# 01.net
KiCad netlist of a schematic drawn in Altium Designer
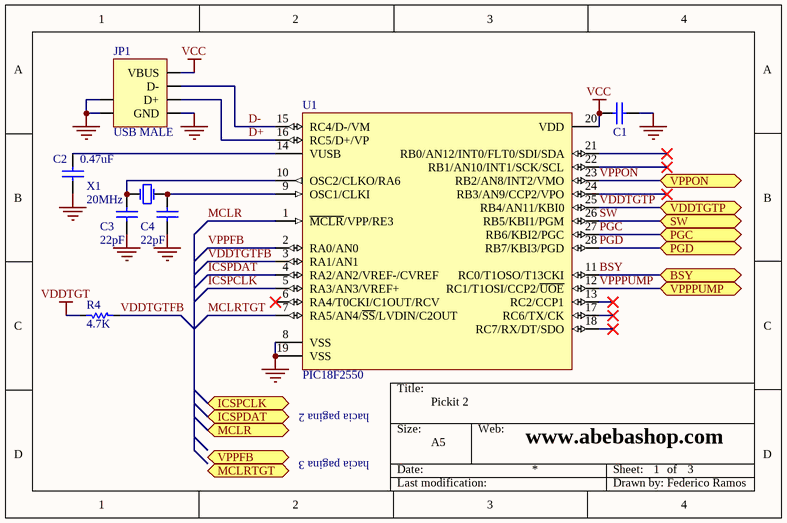
[diagram p0: 01.SchDoc]

(export (version "E")
  (design (tool "Eeschema 10.0.6"))
  (components
    (comp (ref "C1")
      (value "Cap")
      (footprint "1206NP")
      (description "Capacitor")
      (fields (field (name "VOLTAGE") "50V"))
      (libsource (lib "FEDE") (part "Cap"))
    )
    (comp (ref "C2")
      (value "0.47uF")
      (footprint "1206NP")
      (description "Capacitor")
      (fields (field (name "VOLTAGE") "50V") (field (name "Comment") "Cap"))
      (libsource (lib "FEDE") (part "Cap"))
    )
    (comp (ref "C3")
      (value "22pF")
      (footprint "1206NP")
      (description "Capacitor")
      (fields (field (name "VOLTAGE") "50V") (field (name "Comment") "Cap"))
      (libsource (lib "FEDE") (part "Cap"))
    )
    (comp (ref "C4")
      (value "22pF")
      (footprint "1206NP")
      (description "Capacitor")
      (fields (field (name "VOLTAGE") "50V") (field (name "Comment") "Cap"))
      (libsource (lib "FEDE") (part "Cap"))
    )
    (comp (ref "JP1")
      (value "USB MALE")
      (footprint "USB_A_MALE")
      (description "USB Connector")
      (libsource (lib "FEDE") (part "USB"))
    )
    (comp (ref "R4")
      (value "4.7K")
      (footprint "1206NP")
      (description "Resistor")
      (fields (field (name "POWER") "0.25W") (field (name "Comment") "Res"))
      (libsource (lib "FEDE") (part "Res"))
    )
    (comp (ref "U1")
      (value "PIC18F2550")
      (footprint "soic28")
      (description "Enhanced FLASH Microcontroller")
      (libsource (lib "FEDE") (part "PIC18F2550"))
    )
    (comp (ref "X1")
      (value "20MHz")
      (footprint "XTAL1")
      (description "Crystal Oscillator")
      (fields (field (name "Comment") "XTAL"))
      (libsource (lib "FEDE") (part "XTAL"))
    )
  )
  (nets
    (net (code "1") (name "/BSY") (class "Default")
      (node (ref "U1") (pin "11") (pinfunction "RC0/T1OSO/T13CKI_11") (pintype "bidirectional"))
    )
    (net (code "2") (name "/D+") (class "Default")
      (node (ref "JP1") (pin "3") (pinfunction "D+_3") (pintype "passive"))
      (node (ref "U1") (pin "16") (pinfunction "RC5/D+/VP_16") (pintype "bidirectional"))
    )
    (net (code "3") (name "/D-") (class "Default")
      (node (ref "JP1") (pin "2") (pinfunction "D-_2") (pintype "passive"))
      (node (ref "U1") (pin "15") (pinfunction "RC4/D-/VM_15") (pintype "bidirectional"))
    )
    (net (code "4") (name "/ICSPCLK") (class "Default")
      (node (ref "U1") (pin "5") (pinfunction "RA3/AN3/VREF+_5") (pintype "bidirectional"))
    )
    (net (code "5") (name "/ICSPDAT") (class "Default")
      (node (ref "U1") (pin "4") (pinfunction "RA2/AN2/VREF-/CVREF_4") (pintype "bidirectional"))
    )
    (net (code "6") (name "/MCLR") (class "Default")
      (node (ref "U1") (pin "1") (pinfunction "~{MCLR}/VPP/RE3_1") (pintype "input"))
    )
    (net (code "7") (name "/MCLRTGT") (class "Default")
      (node (ref "U1") (pin "7") (pinfunction "RA5/AN4/~{SS}/LVDIN/C2OUT_7") (pintype "bidirectional"))
    )
    (net (code "8") (name "/PGC") (class "Default")
      (node (ref "U1") (pin "27") (pinfunction "RB6/KBI2/PGC_27") (pintype "bidirectional"))
    )
    (net (code "9") (name "/PGD") (class "Default")
      (node (ref "U1") (pin "28") (pinfunction "RB7/KBI3/PGD_28") (pintype "bidirectional"))
    )
    (net (code "10") (name "/SW") (class "Default")
      (node (ref "U1") (pin "26") (pinfunction "RB5/KBI1/PGM_26") (pintype "bidirectional"))
    )
    (net (code "11") (name "/VDDTGTFB") (class "Default")
      (node (ref "R4") (pin "1") (pinfunction "1_1") (pintype "passive"))
      (node (ref "U1") (pin "3") (pinfunction "RA1/AN1_3") (pintype "bidirectional"))
    )
    (net (code "12") (name "/VDDTGTP") (class "Default")
      (node (ref "U1") (pin "25") (pinfunction "RB4/AN11/KBI0_25") (pintype "bidirectional"))
    )
    (net (code "13") (name "/VPPFB") (class "Default")
      (node (ref "U1") (pin "2") (pinfunction "RA0/AN0_2") (pintype "bidirectional"))
    )
    (net (code "14") (name "/VPPON") (class "Default")
      (node (ref "U1") (pin "23") (pinfunction "RB2/AN8/INT2/VMO_23") (pintype "bidirectional"))
    )
    (net (code "15") (name "/VPPPUMP") (class "Default")
      (node (ref "U1") (pin "12") (pinfunction "RC1/T1OSI/CCP2/~{UOE}_12") (pintype "bidirectional"))
    )
    (net (code "16") (name "GND") (class "Default")
      (node (ref "C1") (pin "1") (pinfunction "1_1") (pintype "passive"))
      (node (ref "C2") (pin "1") (pinfunction "1_1") (pintype "passive"))
      (node (ref "C3") (pin "1") (pinfunction "1_1") (pintype "passive"))
      (node (ref "C4") (pin "2") (pinfunction "2_2") (pintype "passive"))
      (node (ref "JP1") (pin "4") (pinfunction "GND_4") (pintype "passive"))
      (node (ref "JP1") (pin "5") (pintype "passive"))
      (node (ref "JP1") (pin "6") (pintype "passive"))
      (node (ref "U1") (pin "19") (pinfunction "VSS_19") (pintype "power_in"))
      (node (ref "U1") (pin "8") (pinfunction "VSS_8") (pintype "power_in"))
    )
    (net (code "17") (name "Net-(U1-OSC1{slash}CLKI)") (class "Default")
      (node (ref "C4") (pin "1") (pinfunction "1_1") (pintype "passive"))
      (node (ref "U1") (pin "9") (pinfunction "OSC1/CLKI_9") (pintype "input"))
      (node (ref "X1") (pin "2") (pinfunction "OSC2_2") (pintype "passive"))
    )
    (net (code "18") (name "Net-(U1-OSC2{slash}CLKO{slash}RA6)") (class "Default")
      (node (ref "C3") (pin "2") (pinfunction "2_2") (pintype "passive"))
      (node (ref "U1") (pin "10") (pinfunction "OSC2/CLKO/RA6_10") (pintype "output"))
      (node (ref "X1") (pin "1") (pinfunction "OSC1_1") (pintype "passive"))
    )
    (net (code "19") (name "Net-(U1-VUSB)") (class "Default")
      (node (ref "C2") (pin "2") (pinfunction "2_2") (pintype "passive"))
      (node (ref "U1") (pin "14") (pinfunction "VUSB_14") (pintype "passive"))
    )
    (net (code "20") (name "VCC") (class "Default")
      (node (ref "C1") (pin "2") (pinfunction "2_2") (pintype "passive"))
      (node (ref "JP1") (pin "1") (pinfunction "VBUS_1") (pintype "passive"))
      (node (ref "U1") (pin "20") (pinfunction "VDD_20") (pintype "power_in"))
    )
    (net (code "21") (name "VDDTGT") (class "Default")
      (node (ref "R4") (pin "2") (pinfunction "2_2") (pintype "passive"))
    )
    (net (code "22") (name "unconnected-(U1-RA4{slash}T0CKI{slash}C1OUT{slash}RCV-Pad6)") (class "Default")
      (node (ref "U1") (pin "6") (pinfunction "RA4/T0CKI/C1OUT/RCV_6") (pintype "bidirectional+no_connect"))
    )
    (net (code "23") (name "unconnected-(U1-RB0{slash}AN12{slash}INT0{slash}FLT0{slash}SDI{slash}SDA-Pad21)") (class "Default")
      (node (ref "U1") (pin "21") (pinfunction "RB0/AN12/INT0/FLT0/SDI/SDA_21") (pintype "bidirectional+no_connect"))
    )
    (net (code "24") (name "unconnected-(U1-RB1{slash}AN10{slash}INT1{slash}SCK{slash}SCL-Pad22)") (class "Default")
      (node (ref "U1") (pin "22") (pinfunction "RB1/AN10/INT1/SCK/SCL_22") (pintype "bidirectional+no_connect"))
    )
    (net (code "25") (name "unconnected-(U1-RB3{slash}AN9{slash}CCP2{slash}VPO-Pad24)") (class "Default")
      (node (ref "U1") (pin "24") (pinfunction "RB3/AN9/CCP2/VPO_24") (pintype "bidirectional+no_connect"))
    )
    (net (code "26") (name "unconnected-(U1-RC2{slash}CCP1-Pad13)") (class "Default")
      (node (ref "U1") (pin "13") (pinfunction "RC2/CCP1_13") (pintype "bidirectional+no_connect"))
    )
    (net (code "27") (name "unconnected-(U1-RC6{slash}TX{slash}CK-Pad17)") (class "Default")
      (node (ref "U1") (pin "17") (pinfunction "RC6/TX/CK_17") (pintype "bidirectional+no_connect"))
    )
    (net (code "28") (name "unconnected-(U1-RC7{slash}RX{slash}DT{slash}SDO-Pad18)") (class "Default")
      (node (ref "U1") (pin "18") (pinfunction "RC7/RX/DT/SDO_18") (pintype "bidirectional+no_connect"))
    )
  )
)
